# praktikum_set.net
KiCad netlist of a schematic drawn in EAGLE
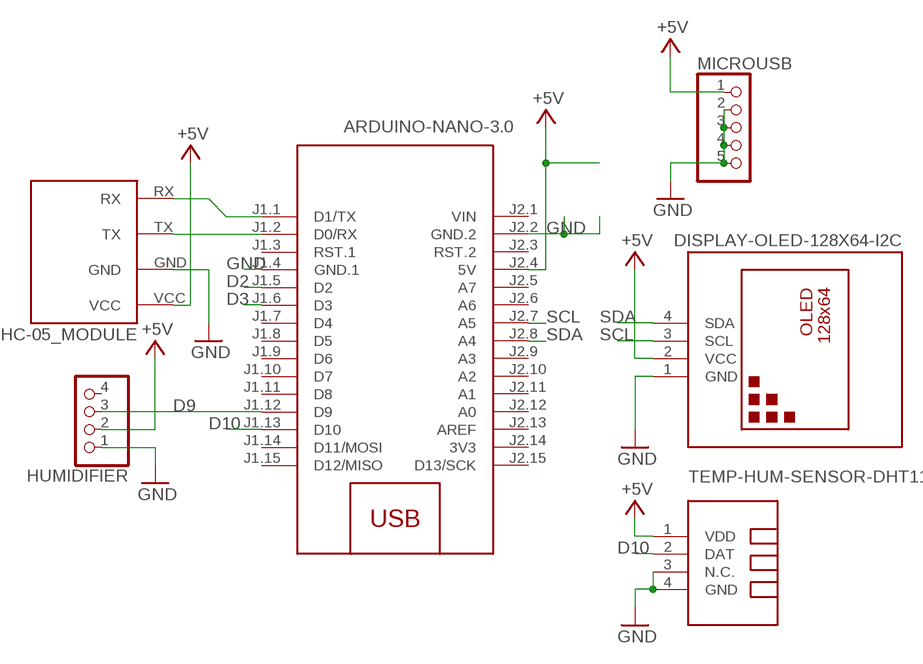
[diagram p0: schematic, sheet 1]

(export (version "E")
  (design (tool "Eeschema 10.0.6"))
  (components
    (comp (ref "DHT11")
      (value "TEMP-HUM-SENSOR-DHT11")
      (footprint "eagle-import:TEMP-HUM-SENSOR-DHT11")
      (libsource (lib "eagle-import") (part "TEMP-HUM-SENSOR-DHT11"))
    )
    (comp (ref "HC-05_MODULE")
      (value "BLUETOOTH_BOARDSTANDING")
      (footprint "eagle-import:BT_BOARD_FOOTPRINT_STANDING")
      (libsource (lib "eagle-import") (part "BLUETOOTH_BOARDSTANDING"))
    )
    (comp (ref "HUMIDIFIER")
      (value "PINHD-1X4")
      (footprint "eagle-import:1X04")
      (libsource (lib "eagle-import") (part "PINHD-1X4"))
    )
    (comp (ref "M1")
      (value "ARDUINO-NANO-3.0")
      (footprint "eagle-import:ARDUINO-NANO-3.0")
      (libsource (lib "eagle-import") (part "ARDUINO-NANO-3.0"))
    )
    (comp (ref "MICROUSB")
      (value "PINHD-1X5")
      (footprint "eagle-import:1X05")
      (libsource (lib "eagle-import") (part "PINHD-1X5"))
    )
    (comp (ref "U$1")
      (value "DISPLAY-OLED-128X64-I2C")
      (footprint "eagle-import:DISPLAY-OLED-128X64-I2C")
      (libsource (lib "eagle-import") (part "DISPLAY-OLED-128X64-I2C"))
    )
  )
  (nets
    (net (code "1") (name "+5V") (class "Default")
      (node (ref "DHT11") (pin "1") (pinfunction "VDD_1") (pintype "power_in"))
      (node (ref "HC-05_MODULE") (pin "VCC") (pinfunction "VCC_VCC") (pintype "bidirectional"))
      (node (ref "HUMIDIFIER") (pin "2") (pinfunction "2_2") (pintype "passive"))
      (node (ref "M1") (pin "J2.4") (pinfunction "5V_J2.4") (pintype "power_in"))
      (node (ref "MICROUSB") (pin "1") (pinfunction "1_1") (pintype "passive"))
      (node (ref "U$1") (pin "2") (pinfunction "VCC_2") (pintype "power_in"))
    )
    (net (code "2") (name "/3V3") (class "Default")
      (node (ref "M1") (pin "J2.14") (pinfunction "3V3_J2.14") (pintype "power_in"))
    )
    (net (code "3") (name "/D2") (class "Default")
      (node (ref "M1") (pin "J1.5") (pinfunction "D2_J1.5") (pintype "bidirectional"))
    )
    (net (code "4") (name "/D3") (class "Default")
      (node (ref "M1") (pin "J1.6") (pinfunction "D3_J1.6") (pintype "bidirectional"))
    )
    (net (code "5") (name "/D9") (class "Default")
      (node (ref "HUMIDIFIER") (pin "3") (pinfunction "3_3") (pintype "passive"))
      (node (ref "M1") (pin "J1.12") (pinfunction "D9_J1.12") (pintype "bidirectional"))
    )
    (net (code "6") (name "/D10") (class "Default")
      (node (ref "DHT11") (pin "2") (pinfunction "DAT_2") (pintype "bidirectional"))
      (node (ref "M1") (pin "J1.13") (pinfunction "D10_J1.13") (pintype "bidirectional"))
    )
    (net (code "7") (name "/SCL") (class "Default")
      (node (ref "M1") (pin "J2.7") (pinfunction "A5_J2.7") (pintype "bidirectional"))
      (node (ref "U$1") (pin "3") (pinfunction "SCL_3") (pintype "bidirectional"))
    )
    (net (code "8") (name "/SDA") (class "Default")
      (node (ref "M1") (pin "J2.8") (pinfunction "A4_J2.8") (pintype "bidirectional"))
      (node (ref "U$1") (pin "4") (pinfunction "SDA_4") (pintype "bidirectional"))
    )
    (net (code "9") (name "/VIN") (class "Default")
      (node (ref "M1") (pin "J2.1") (pinfunction "VIN_J2.1") (pintype "power_in"))
    )
    (net (code "10") (name "GND") (class "Default")
      (node (ref "DHT11") (pin "3") (pinfunction "N.C._3") (pintype "passive"))
      (node (ref "DHT11") (pin "4") (pinfunction "GND_4") (pintype "power_in"))
      (node (ref "HC-05_MODULE") (pin "GND") (pinfunction "GND_GND") (pintype "bidirectional"))
      (node (ref "HUMIDIFIER") (pin "1") (pinfunction "1_1") (pintype "passive"))
      (node (ref "M1") (pin "J1.4") (pinfunction "GND.1_J1.4") (pintype "power_in"))
      (node (ref "M1") (pin "J2.2") (pinfunction "GND.2_J2.2") (pintype "power_in"))
      (node (ref "MICROUSB") (pin "2") (pinfunction "2_2") (pintype "passive"))
      (node (ref "MICROUSB") (pin "3") (pinfunction "3_3") (pintype "passive"))
      (node (ref "MICROUSB") (pin "4") (pinfunction "4_4") (pintype "passive"))
      (node (ref "MICROUSB") (pin "5") (pinfunction "5_5") (pintype "passive"))
      (node (ref "U$1") (pin "1") (pinfunction "GND_1") (pintype "power_in"))
    )
    (net (code "11") (name "Net-(M1-D0{slash}RX)") (class "Default")
      (node (ref "HC-05_MODULE") (pin "TX") (pinfunction "TX_TX") (pintype "bidirectional"))
      (node (ref "M1") (pin "J1.2") (pinfunction "D0/RX_J1.2") (pintype "bidirectional"))
    )
    (net (code "12") (name "Net-(M1-D1{slash}TX)") (class "Default")
      (node (ref "HC-05_MODULE") (pin "RX") (pinfunction "RX_RX") (pintype "bidirectional"))
      (node (ref "M1") (pin "J1.1") (pinfunction "D1/TX_J1.1") (pintype "bidirectional"))
    )
    (net (code "13") (name "unconnected-(HUMIDIFIER-Pad4)") (class "Default")
      (node (ref "HUMIDIFIER") (pin "4") (pinfunction "4_4") (pintype "passive"))
    )
    (net (code "14") (name "unconnected-(M1-A0-PadJ2.12)") (class "Default")
      (node (ref "M1") (pin "J2.12") (pinfunction "A0_J2.12") (pintype "bidirectional"))
    )
    (net (code "15") (name "unconnected-(M1-A1-PadJ2.11)") (class "Default")
      (node (ref "M1") (pin "J2.11") (pinfunction "A1_J2.11") (pintype "bidirectional"))
    )
    (net (code "16") (name "unconnected-(M1-A2-PadJ2.10)") (class "Default")
      (node (ref "M1") (pin "J2.10") (pinfunction "A2_J2.10") (pintype "bidirectional"))
    )
    (net (code "17") (name "unconnected-(M1-A3-PadJ2.9)") (class "Default")
      (node (ref "M1") (pin "J2.9") (pinfunction "A3_J2.9") (pintype "bidirectional"))
    )
    (net (code "18") (name "unconnected-(M1-A6-PadJ2.6)") (class "Default")
      (node (ref "M1") (pin "J2.6") (pinfunction "A6_J2.6") (pintype "bidirectional"))
    )
    (net (code "19") (name "unconnected-(M1-A7-PadJ2.5)") (class "Default")
      (node (ref "M1") (pin "J2.5") (pinfunction "A7_J2.5") (pintype "bidirectional"))
    )
    (net (code "20") (name "unconnected-(M1-AREF-PadJ2.13)") (class "Default")
      (node (ref "M1") (pin "J2.13") (pinfunction "AREF_J2.13") (pintype "bidirectional"))
    )
    (net (code "21") (name "unconnected-(M1-D4-PadJ1.7)") (class "Default")
      (node (ref "M1") (pin "J1.7") (pinfunction "D4_J1.7") (pintype "bidirectional"))
    )
    (net (code "22") (name "unconnected-(M1-D5-PadJ1.8)") (class "Default")
      (node (ref "M1") (pin "J1.8") (pinfunction "D5_J1.8") (pintype "bidirectional"))
    )
    (net (code "23") (name "unconnected-(M1-D6-PadJ1.9)") (class "Default")
      (node (ref "M1") (pin "J1.9") (pinfunction "D6_J1.9") (pintype "bidirectional"))
    )
    (net (code "24") (name "unconnected-(M1-D7-PadJ1.10)") (class "Default")
      (node (ref "M1") (pin "J1.10") (pinfunction "D7_J1.10") (pintype "bidirectional"))
    )
    (net (code "25") (name "unconnected-(M1-D8-PadJ1.11)") (class "Default")
      (node (ref "M1") (pin "J1.11") (pinfunction "D8_J1.11") (pintype "bidirectional"))
    )
    (net (code "26") (name "unconnected-(M1-D11{slash}MOSI-PadJ1.14)") (class "Default")
      (node (ref "M1") (pin "J1.14") (pinfunction "D11/MOSI_J1.14") (pintype "bidirectional"))
    )
    (net (code "27") (name "unconnected-(M1-D12{slash}MISO-PadJ1.15)") (class "Default")
      (node (ref "M1") (pin "J1.15") (pinfunction "D12/MISO_J1.15") (pintype "bidirectional"))
    )
    (net (code "28") (name "unconnected-(M1-D13{slash}SCK-PadJ2.15)") (class "Default")
      (node (ref "M1") (pin "J2.15") (pinfunction "D13/SCK_J2.15") (pintype "bidirectional"))
    )
    (net (code "29") (name "unconnected-(M1-RST.1-PadJ1.3)") (class "Default")
      (node (ref "M1") (pin "J1.3") (pinfunction "RST.1_J1.3") (pintype "bidirectional"))
    )
    (net (code "30") (name "unconnected-(M1-RST.2-PadJ2.3)") (class "Default")
      (node (ref "M1") (pin "J2.3") (pinfunction "RST.2_J2.3") (pintype "bidirectional"))
    )
  )
)
